# GainBlock.net
KiCad netlist of a schematic drawn in EAGLE
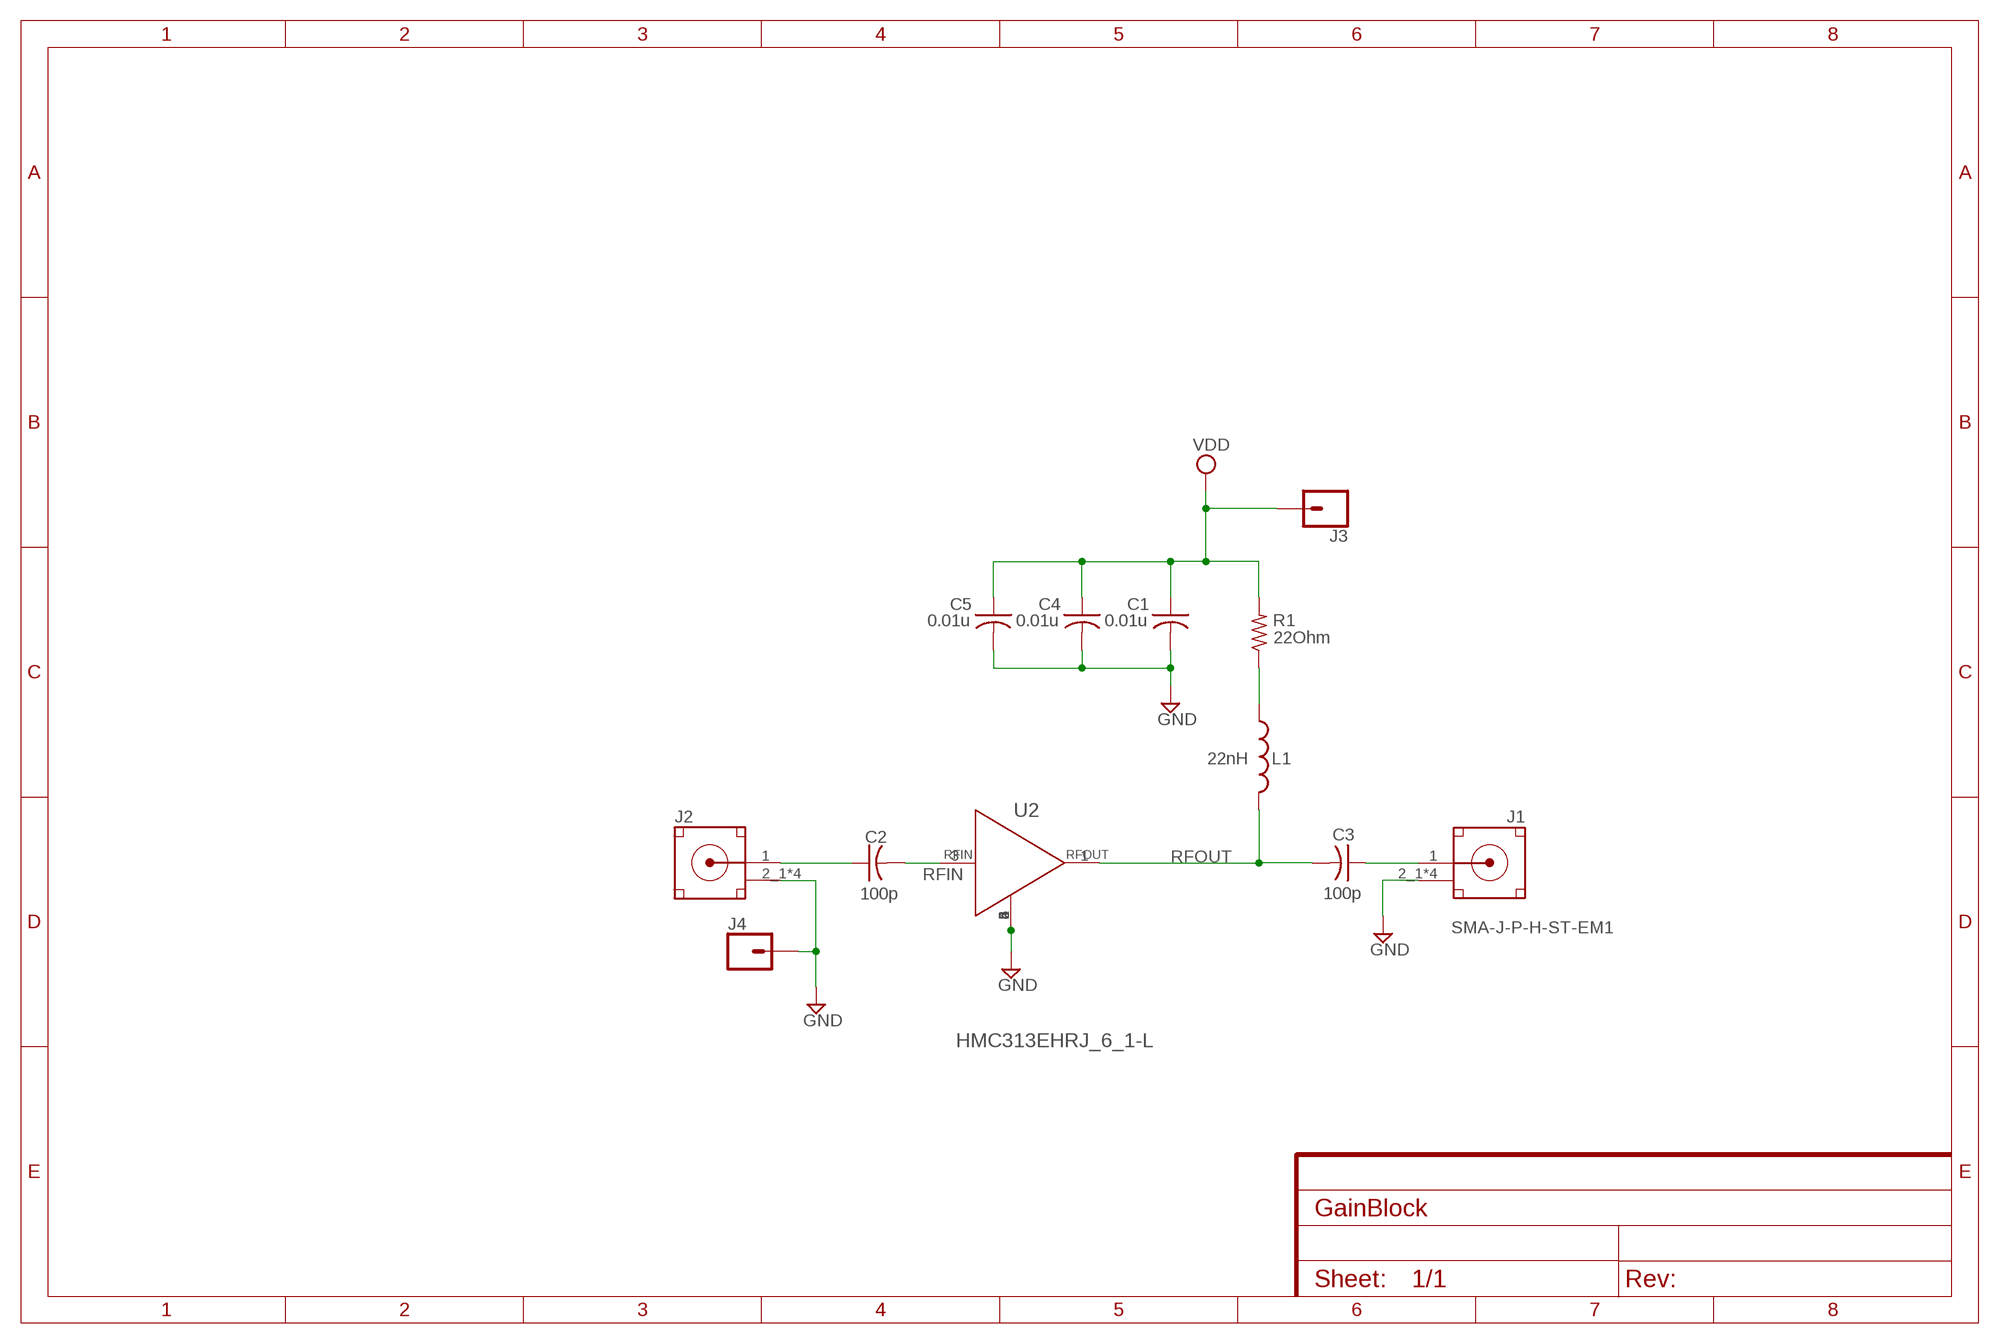
[diagram p0: schematic, sheet 1]

(export (version "E")
  (design (tool "Eeschema 10.0.6"))
  (components
    (comp (ref "C1")
      (value "0.01u")
      (footprint "eagle-import:C0805")
      (libsource (lib "eagle-import") (part "C-USC0805"))
    )
    (comp (ref "C2")
      (value "100p")
      (footprint "eagle-import:C0805")
      (libsource (lib "eagle-import") (part "C-USC0805"))
    )
    (comp (ref "C3")
      (value "100p")
      (footprint "eagle-import:C0805")
      (libsource (lib "eagle-import") (part "C-USC0805"))
    )
    (comp (ref "C4")
      (value "0.01u")
      (footprint "eagle-import:C0805")
      (libsource (lib "eagle-import") (part "C-USC0805"))
    )
    (comp (ref "C5")
      (value "0.01u")
      (footprint "eagle-import:C0805")
      (libsource (lib "eagle-import") (part "C-USC0805"))
    )
    (comp (ref "J1")
      (value "SMA-J-P-H-ST-EM1")
      (footprint "eagle-import:SMA-J-P-H-ST-EM1")
      (fields (field (name "DIGI-KEY_PART_NUMBER") "SAM8857-ND") (field (name "MF") "Samtec"))
      (libsource (lib "eagle-import") (part "SMA-J-P-H-ST-EM1"))
    )
    (comp (ref "J2")
      (value "SMA-J-P-H-ST-EM1")
      (footprint "eagle-import:SMA-J-P-H-ST-EM1")
      (fields (field (name "DIGI-KEY_PART_NUMBER") "SAM8857-ND") (field (name "MF") "Samtec"))
      (libsource (lib "eagle-import") (part "SMA-J-P-H-ST-EM1"))
    )
    (comp (ref "J3")
      (value "CONN_01")
      (footprint "eagle-import:1X01")
      (libsource (lib "eagle-import") (part "CONN_01"))
    )
    (comp (ref "J4")
      (value "CONN_01")
      (footprint "eagle-import:1X01")
      (libsource (lib "eagle-import") (part "CONN_01"))
    )
    (comp (ref "L1")
      (value "22nH")
      (footprint "eagle-import:L0805")
      (libsource (lib "eagle-import") (part "L-USL0805"))
    )
    (comp (ref "R1")
      (value "22Ohm")
      (footprint "eagle-import:R0805")
      (libsource (lib "eagle-import") (part "R-US_R0805"))
    )
    (comp (ref "U2")
      (value "HMC313EHRJ_6_1-L")
      (footprint "eagle-import:HRJ_6_1-L")
      (fields (field (name "MANUFACTURER_PART_NUMBER") "HMC313E"))
      (libsource (lib "eagle-import") (part "HMC313EHRJ_6_1-L"))
    )
  )
  (nets
    (net (code "1") (name "/RFIN") (class "Default")
      (node (ref "C2") (pin "2") (pinfunction "2_2") (pintype "passive"))
      (node (ref "U2") (pin "3") (pinfunction "RFIN_3") (pintype "passive"))
    )
    (net (code "2") (name "/RFOUT") (class "Default")
      (node (ref "C3") (pin "2") (pinfunction "2_2") (pintype "passive"))
      (node (ref "L1") (pin "2") (pinfunction "2_2") (pintype "passive"))
      (node (ref "U2") (pin "1") (pinfunction "RFOUT_1") (pintype "passive"))
    )
    (net (code "3") (name "GND") (class "Default")
      (node (ref "C1") (pin "2") (pinfunction "2_2") (pintype "passive"))
      (node (ref "C4") (pin "2") (pinfunction "2_2") (pintype "passive"))
      (node (ref "C5") (pin "2") (pinfunction "2_2") (pintype "passive"))
      (node (ref "J1") (pin "2_1") (pinfunction "GND_2_1") (pintype "power_in"))
      (node (ref "J1") (pin "2_2") (pinfunction "GND_2_2") (pintype "power_in"))
      (node (ref "J1") (pin "3_1") (pinfunction "GND_3_1") (pintype "power_in"))
      (node (ref "J1") (pin "3_2") (pinfunction "GND_3_2") (pintype "power_in"))
      (node (ref "J2") (pin "2_1") (pinfunction "GND_2_1") (pintype "power_in"))
      (node (ref "J2") (pin "2_2") (pinfunction "GND_2_2") (pintype "power_in"))
      (node (ref "J2") (pin "3_1") (pinfunction "GND_3_1") (pintype "power_in"))
      (node (ref "J2") (pin "3_2") (pinfunction "GND_3_2") (pintype "power_in"))
      (node (ref "J4") (pin "1") (pinfunction "1_1") (pintype "passive"))
      (node (ref "U2") (pin "2") (pinfunction "GND_2_2") (pintype "passive"))
      (node (ref "U2") (pin "4") (pinfunction "GND_3_4") (pintype "passive"))
      (node (ref "U2") (pin "5") (pinfunction "GND_4_5") (pintype "passive"))
      (node (ref "U2") (pin "6") (pinfunction "GND_6") (pintype "passive"))
    )
    (net (code "4") (name "Net-(J1-SIGNAL)") (class "Default")
      (node (ref "C3") (pin "1") (pinfunction "1_1") (pintype "passive"))
      (node (ref "J1") (pin "1") (pinfunction "SIGNAL_1") (pintype "passive"))
    )
    (net (code "5") (name "Net-(J2-SIGNAL)") (class "Default")
      (node (ref "C2") (pin "1") (pinfunction "1_1") (pintype "passive"))
      (node (ref "J2") (pin "1") (pinfunction "SIGNAL_1") (pintype "passive"))
    )
    (net (code "6") (name "Net-(L1-Pad1)") (class "Default")
      (node (ref "L1") (pin "1") (pinfunction "1_1") (pintype "passive"))
      (node (ref "R1") (pin "1") (pinfunction "1_1") (pintype "passive"))
    )
    (net (code "7") (name "VDD") (class "Default")
      (node (ref "C1") (pin "1") (pinfunction "1_1") (pintype "passive"))
      (node (ref "C4") (pin "1") (pinfunction "1_1") (pintype "passive"))
      (node (ref "C5") (pin "1") (pinfunction "1_1") (pintype "passive"))
      (node (ref "J3") (pin "1") (pinfunction "1_1") (pintype "passive"))
      (node (ref "R1") (pin "2") (pinfunction "2_2") (pintype "passive"))
    )
  )
)
